# LPC1343_BaseBoard_V1_6.net
KiCad netlist of a schematic drawn in EAGLE
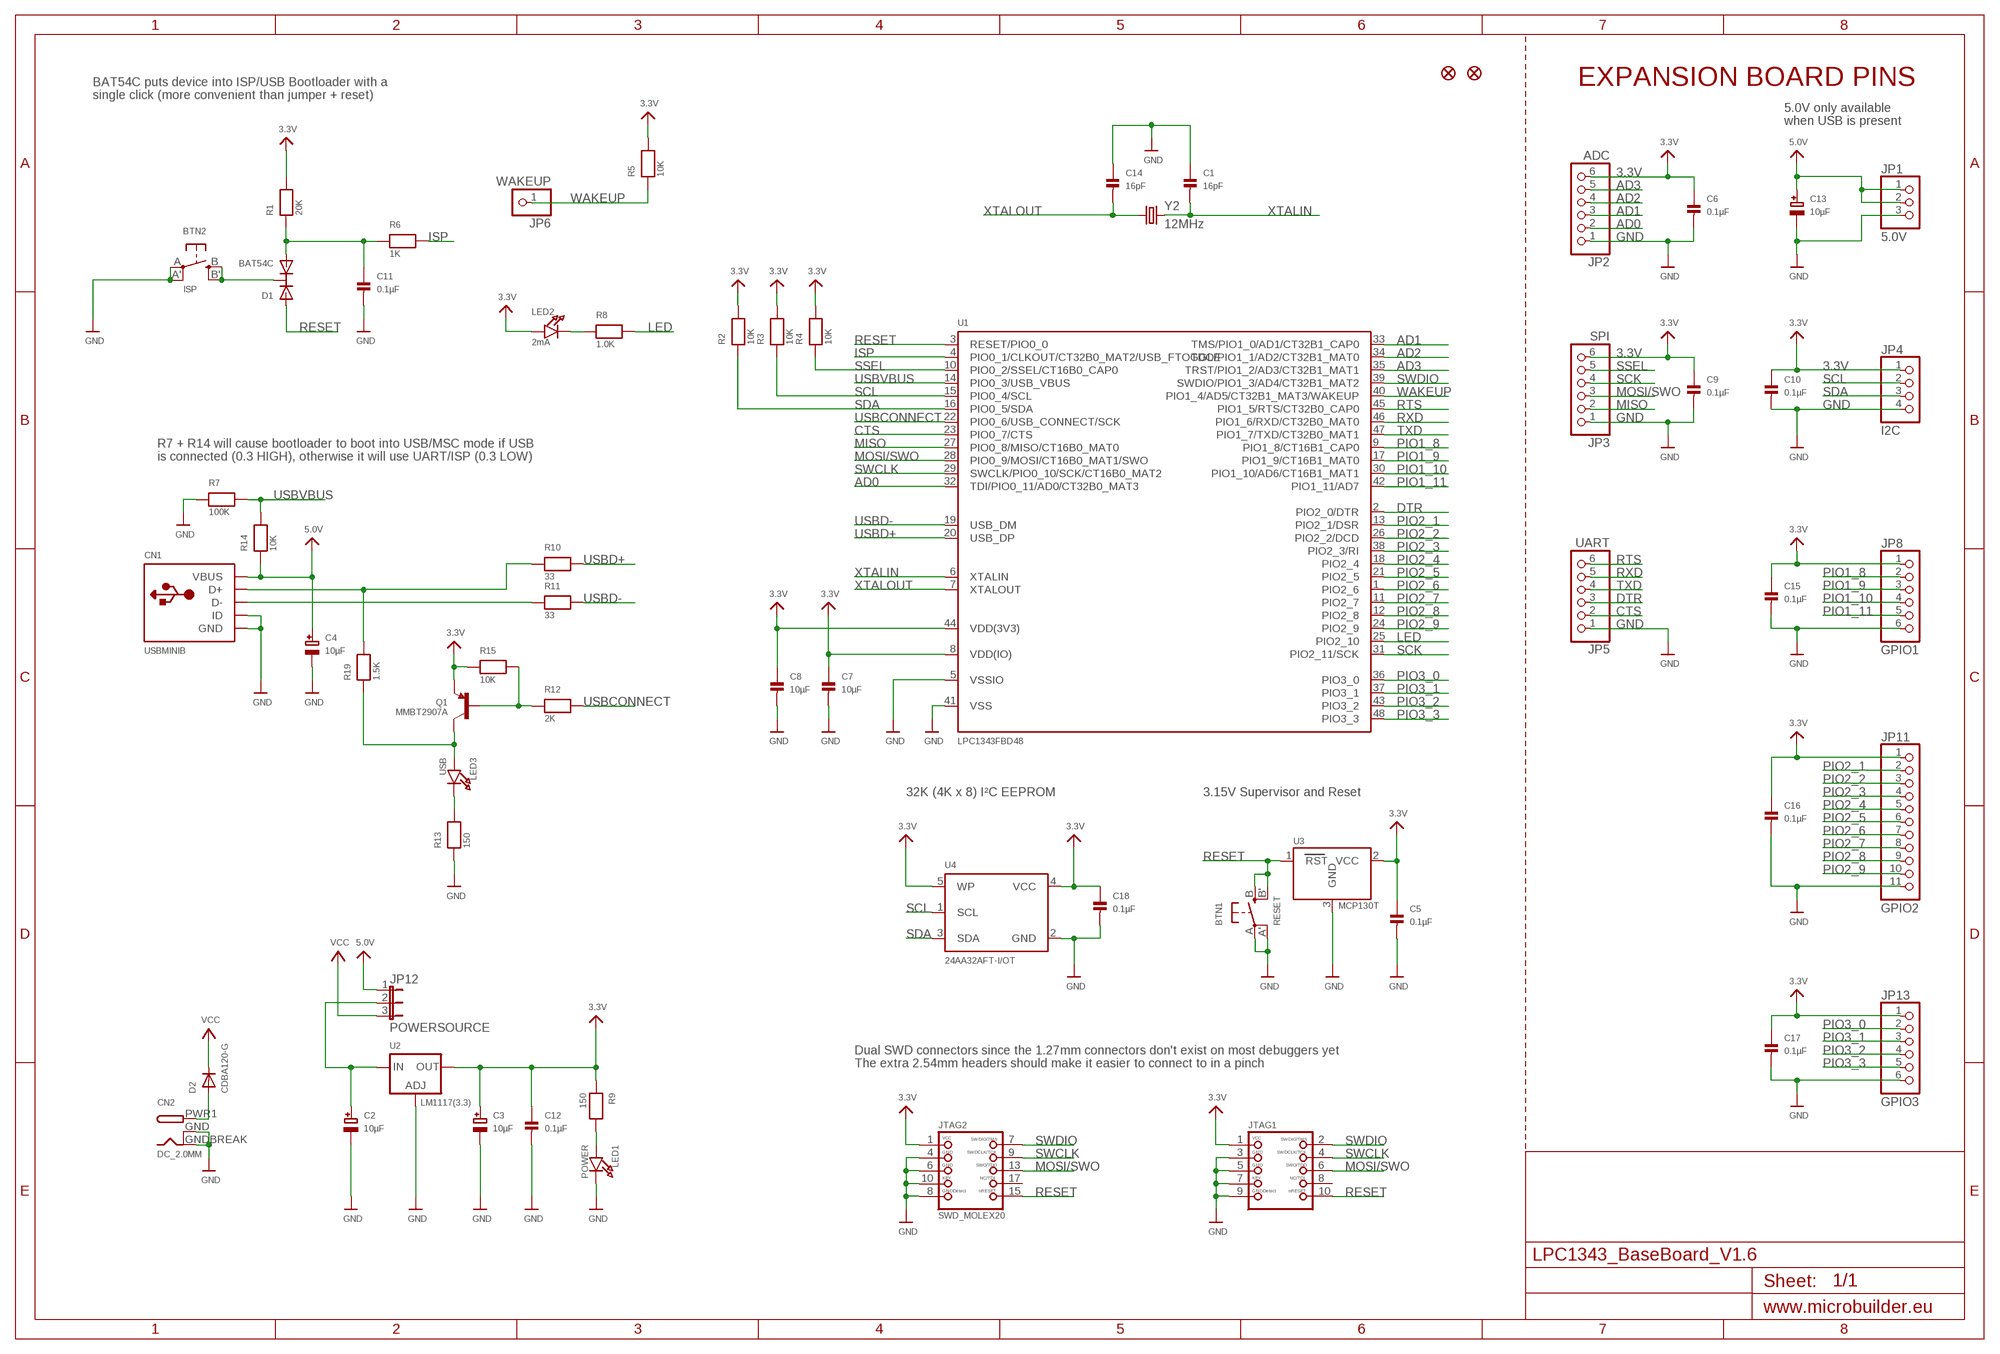
[diagram p0: schematic, sheet 1]

(export (version "E")
  (design (tool "Eeschema 10.0.6"))
  (components
    (comp (ref "BTN1")
      (value "RESET")
      (footprint "eagle-import:EVQ-Q2")
      (libsource (lib "eagle-import") (part "BUTTON_SMT"))
    )
    (comp (ref "BTN2")
      (value "ISP")
      (footprint "eagle-import:EVQ-Q2")
      (libsource (lib "eagle-import") (part "BUTTON_SMT"))
    )
    (comp (ref "C1")
      (value "16pF")
      (footprint "eagle-import:0603")
      (libsource (lib "eagle-import") (part "CAP_CERAMIC0603"))
    )
    (comp (ref "C2")
      (value "10µF")
      (footprint "eagle-import:EIA3216-18_A-R")
      (libsource (lib "eagle-import") (part "CAP_TANTALUMA/3216_REFLOW"))
    )
    (comp (ref "C3")
      (value "10µF")
      (footprint "eagle-import:EIA3216-18_A-R")
      (libsource (lib "eagle-import") (part "CAP_TANTALUMA/3216_REFLOW"))
    )
    (comp (ref "C4")
      (value "10µF")
      (footprint "eagle-import:EIA3216-18_A-R")
      (libsource (lib "eagle-import") (part "CAP_TANTALUMA/3216_REFLOW"))
    )
    (comp (ref "C5")
      (value "0.1µF")
      (footprint "eagle-import:0603")
      (libsource (lib "eagle-import") (part "CAP_CERAMIC0603"))
    )
    (comp (ref "C6")
      (value "0.1µF")
      (footprint "eagle-import:0603")
      (libsource (lib "eagle-import") (part "CAP_CERAMIC0603"))
    )
    (comp (ref "C7")
      (value "10µF")
      (footprint "eagle-import:0805")
      (libsource (lib "eagle-import") (part "CAP_CERAMIC0805"))
    )
    (comp (ref "C8")
      (value "10µF")
      (footprint "eagle-import:0805")
      (libsource (lib "eagle-import") (part "CAP_CERAMIC0805"))
    )
    (comp (ref "C9")
      (value "0.1µF")
      (footprint "eagle-import:0603")
      (libsource (lib "eagle-import") (part "CAP_CERAMIC0603"))
    )
    (comp (ref "C10")
      (value "0.1µF")
      (footprint "eagle-import:0603")
      (libsource (lib "eagle-import") (part "CAP_CERAMIC0603"))
    )
    (comp (ref "C11")
      (value "0.1µF")
      (footprint "eagle-import:0603")
      (libsource (lib "eagle-import") (part "CAP_CERAMIC0603"))
    )
    (comp (ref "C12")
      (value "0.1µF")
      (footprint "eagle-import:0603")
      (libsource (lib "eagle-import") (part "CAP_CERAMIC0603"))
    )
    (comp (ref "C13")
      (value "10µF")
      (footprint "eagle-import:EIA3216-18_A-R")
      (libsource (lib "eagle-import") (part "CAP_TANTALUMA/3216_REFLOW"))
    )
    (comp (ref "C14")
      (value "16pF")
      (footprint "eagle-import:0603")
      (libsource (lib "eagle-import") (part "CAP_CERAMIC0603"))
    )
    (comp (ref "C15")
      (value "0.1µF")
      (footprint "eagle-import:0603")
      (libsource (lib "eagle-import") (part "CAP_CERAMIC0603"))
    )
    (comp (ref "C16")
      (value "0.1µF")
      (footprint "eagle-import:0603")
      (libsource (lib "eagle-import") (part "CAP_CERAMIC0603"))
    )
    (comp (ref "C17")
      (value "0.1µF")
      (footprint "eagle-import:0603")
      (libsource (lib "eagle-import") (part "CAP_CERAMIC0603"))
    )
    (comp (ref "C18")
      (value "0.1µF")
      (footprint "eagle-import:0603")
      (libsource (lib "eagle-import") (part "CAP_CERAMIC0603"))
    )
    (comp (ref "CN1")
      (value "USBMINIB")
      (footprint "eagle-import:USB-MINIB")
      (libsource (lib "eagle-import") (part "USBMINIB"))
    )
    (comp (ref "CN2")
      (value "DC_2.0MM")
      (footprint "eagle-import:DCJACK_2MM_SMT")
      (libsource (lib "eagle-import") (part "DCBARRELSMT"))
    )
    (comp (ref "D1")
      (value "BAT54C")
      (footprint "eagle-import:SOT23-R")
      (libsource (lib "eagle-import") (part "BAT54C"))
    )
    (comp (ref "D2")
      (value "CDBA120-G")
      (footprint "eagle-import:SMADIODE")
      (libsource (lib "eagle-import") (part "DIODESMA"))
    )
    (comp (ref "JP1")
      (value "5.0V")
      (footprint "eagle-import:1X03_ROUND")
      (libsource (lib "eagle-import") (part "HEADER-1X3ROUND"))
    )
    (comp (ref "JP2")
      (value "ADC")
      (footprint "eagle-import:1X06_ROUND")
      (libsource (lib "eagle-import") (part "HEADER-1X6ROUND"))
    )
    (comp (ref "JP3")
      (value "SPI")
      (footprint "eagle-import:1X06_ROUND")
      (libsource (lib "eagle-import") (part "HEADER-1X6ROUND"))
    )
    (comp (ref "JP4")
      (value "I2C")
      (footprint "eagle-import:1X04_ROUND")
      (libsource (lib "eagle-import") (part "HEADER-1X4ROUND"))
    )
    (comp (ref "JP5")
      (value "UART")
      (footprint "eagle-import:1X06_ROUND")
      (libsource (lib "eagle-import") (part "HEADER-1X6ROUND"))
    )
    (comp (ref "JP6")
      (value "WAKEUP")
      (footprint "eagle-import:1X01_ROUND")
      (libsource (lib "eagle-import") (part "HEADER-1X1ROUND"))
    )
    (comp (ref "JP7")
      (value "FIDUCIAL1X2.5")
      (footprint "eagle-import:FIDUCIAL-1X2.5")
      (libsource (lib "eagle-import") (part "FIDUCIAL1X2.5"))
    )
    (comp (ref "JP8")
      (value "GPIO1")
      (footprint "eagle-import:1X06_ROUND")
      (libsource (lib "eagle-import") (part "HEADER-1X6ROUND"))
    )
    (comp (ref "JP9")
      (value "FIDUCIAL1X2.5")
      (footprint "eagle-import:FIDUCIAL-1X2.5")
      (libsource (lib "eagle-import") (part "FIDUCIAL1X2.5"))
    )
    (comp (ref "JP11")
      (value "GPIO2")
      (footprint "eagle-import:1X11_ROUND")
      (libsource (lib "eagle-import") (part "HEADER-1X11"))
    )
    (comp (ref "JP12")
      (value "POWERSOURCE")
      (footprint "eagle-import:JUMPER3")
      (libsource (lib "eagle-import") (part "JUMPER3"))
    )
    (comp (ref "JP13")
      (value "GPIO3")
      (footprint "eagle-import:1X06_ROUND")
      (libsource (lib "eagle-import") (part "HEADER-1X6ROUND"))
    )
    (comp (ref "JTAG1")
      (value "JTAG-CORTEXM3")
      (footprint "eagle-import:2X05_1.27MM_SMT")
      (libsource (lib "eagle-import") (part "JTAG-CORTEXM3"))
    )
    (comp (ref "JTAG2")
      (value "SWD_MOLEX20")
      (footprint "eagle-import:JTAG-ARM")
      (libsource (lib "eagle-import") (part "JTAG-CORTEXM3MOLEX20"))
    )
    (comp (ref "LED1")
      (value "POWER")
      (footprint "eagle-import:CHIPLED_0805")
      (libsource (lib "eagle-import") (part "LED0805"))
    )
    (comp (ref "LED2")
      (value "2mA")
      (footprint "eagle-import:CHIPLED_0805")
      (libsource (lib "eagle-import") (part "LED0805"))
    )
    (comp (ref "LED3")
      (value "USB")
      (footprint "eagle-import:CHIPLED_0805")
      (libsource (lib "eagle-import") (part "LED0805"))
    )
    (comp (ref "Q1")
      (value "MMBT2907A")
      (footprint "eagle-import:SOT23-R")
      (libsource (lib "eagle-import") (part "TRANSISTOR_PNPSOT23-REFLOW"))
    )
    (comp (ref "R1")
      (value "20K")
      (footprint "eagle-import:0603")
      (libsource (lib "eagle-import") (part "RESISTOR0603"))
    )
    (comp (ref "R2")
      (value "10K")
      (footprint "eagle-import:0603")
      (libsource (lib "eagle-import") (part "RESISTOR0603"))
    )
    (comp (ref "R3")
      (value "10K")
      (footprint "eagle-import:0603")
      (libsource (lib "eagle-import") (part "RESISTOR0603"))
    )
    (comp (ref "R4")
      (value "10K")
      (footprint "eagle-import:0603")
      (libsource (lib "eagle-import") (part "RESISTOR0603"))
    )
    (comp (ref "R5")
      (value "10K")
      (footprint "eagle-import:0603")
      (libsource (lib "eagle-import") (part "RESISTOR0603"))
    )
    (comp (ref "R6")
      (value "1K")
      (footprint "eagle-import:0603")
      (libsource (lib "eagle-import") (part "RESISTOR0603"))
    )
    (comp (ref "R7")
      (value "100K")
      (footprint "eagle-import:0603")
      (libsource (lib "eagle-import") (part "RESISTOR0603"))
    )
    (comp (ref "R8")
      (value "1.0K")
      (footprint "eagle-import:0603")
      (libsource (lib "eagle-import") (part "RESISTOR0603"))
    )
    (comp (ref "R9")
      (value "150")
      (footprint "eagle-import:0603")
      (libsource (lib "eagle-import") (part "RESISTOR0603"))
    )
    (comp (ref "R10")
      (value "33")
      (footprint "eagle-import:0603")
      (libsource (lib "eagle-import") (part "RESISTOR0603"))
    )
    (comp (ref "R11")
      (value "33")
      (footprint "eagle-import:0603")
      (libsource (lib "eagle-import") (part "RESISTOR0603"))
    )
    (comp (ref "R12")
      (value "2K")
      (footprint "eagle-import:0603")
      (libsource (lib "eagle-import") (part "RESISTOR0603"))
    )
    (comp (ref "R13")
      (value "150")
      (footprint "eagle-import:0603")
      (libsource (lib "eagle-import") (part "RESISTOR0603"))
    )
    (comp (ref "R14")
      (value "10K")
      (footprint "eagle-import:0603")
      (libsource (lib "eagle-import") (part "RESISTOR0603"))
    )
    (comp (ref "R15")
      (value "10K")
      (footprint "eagle-import:0603")
      (libsource (lib "eagle-import") (part "RESISTOR0603"))
    )
    (comp (ref "R19")
      (value "1.5K")
      (footprint "eagle-import:0603")
      (libsource (lib "eagle-import") (part "RESISTOR0603"))
    )
    (comp (ref "U1")
      (value "LPC1343FBD48")
      (footprint "eagle-import:LQFP48")
      (libsource (lib "eagle-import") (part "LPC1343_QFP"))
    )
    (comp (ref "U2")
      (value "LM1117(3.3)")
      (footprint "eagle-import:SOT223-R")
      (libsource (lib "eagle-import") (part "LM1117SOT223-REFLOW"))
    )
    (comp (ref "U3")
      (value "MCP130T")
      (footprint "eagle-import:SOT23-R")
      (libsource (lib "eagle-import") (part "MCP130TREFLOW"))
    )
    (comp (ref "U4")
      (value "24AA32AFT-I/OT")
      (footprint "eagle-import:SOT23-5")
      (libsource (lib "eagle-import") (part "MCP24AA32"))
    )
    (comp (ref "Y2")
      (value "12MHz")
      (footprint "eagle-import:HC49_S")
      (libsource (lib "eagle-import") (part "CRYSTALHC49S"))
    )
  )
  (nets
    (net (code "1") (name "/AD0") (class "Default")
      (node (ref "JP2") (pin "2") (pinfunction "2_2") (pintype "passive"))
      (node (ref "U1") (pin "32") (pinfunction "TDI/PIO0_11/AD0/CT32B0_MAT3_32") (pintype "bidirectional"))
    )
    (net (code "2") (name "/AD1") (class "Default")
      (node (ref "JP2") (pin "3") (pinfunction "3_3") (pintype "passive"))
      (node (ref "U1") (pin "33") (pinfunction "TMS/PIO1_0/AD1/CT32B1_CAP0_33") (pintype "bidirectional"))
    )
    (net (code "3") (name "/AD2") (class "Default")
      (node (ref "JP2") (pin "4") (pinfunction "4_4") (pintype "passive"))
      (node (ref "U1") (pin "34") (pinfunction "TDO/PIO1_1/AD2/CT32B1_MAT0_34") (pintype "bidirectional"))
    )
    (net (code "4") (name "/AD3") (class "Default")
      (node (ref "JP2") (pin "5") (pinfunction "5_5") (pintype "passive"))
      (node (ref "U1") (pin "35") (pinfunction "TRST/PIO1_2/AD3/CT32B1_MAT1_35") (pintype "bidirectional"))
    )
    (net (code "5") (name "/CTS") (class "Default")
      (node (ref "JP5") (pin "2") (pinfunction "2_2") (pintype "passive"))
      (node (ref "U1") (pin "23") (pinfunction "PIO0_7/CTS_23") (pintype "bidirectional"))
    )
    (net (code "6") (name "/DTR") (class "Default")
      (node (ref "JP5") (pin "3") (pinfunction "3_3") (pintype "passive"))
      (node (ref "U1") (pin "2") (pinfunction "PIO2_0/DTR_2") (pintype "bidirectional"))
    )
    (net (code "7") (name "/ISP") (class "Default")
      (node (ref "R6") (pin "2") (pinfunction "2_2") (pintype "passive"))
      (node (ref "U1") (pin "4") (pinfunction "PIO0_1/CLKOUT/CT32B0_MAT2/USB_FTOGGLE_4") (pintype "bidirectional"))
    )
    (net (code "8") (name "/LED") (class "Default")
      (node (ref "R8") (pin "2") (pinfunction "2_2") (pintype "passive"))
      (node (ref "U1") (pin "25") (pinfunction "PIO2_10_25") (pintype "bidirectional"))
    )
    (net (code "9") (name "/MISO") (class "Default")
      (node (ref "JP3") (pin "2") (pinfunction "2_2") (pintype "passive"))
      (node (ref "U1") (pin "27") (pinfunction "PIO0_8/MISO/CT16B0_MAT0_27") (pintype "bidirectional"))
    )
    (net (code "10") (name "/MOSI{slash}SWO") (class "Default")
      (node (ref "JP3") (pin "3") (pinfunction "3_3") (pintype "passive"))
      (node (ref "JTAG1") (pin "6") (pinfunction "6_6") (pintype "passive"))
      (node (ref "JTAG2") (pin "13") (pinfunction "6_13") (pintype "passive"))
      (node (ref "U1") (pin "28") (pinfunction "PIO0_9/MOSI/CT16B0_MAT1/SWO_28") (pintype "bidirectional"))
    )
    (net (code "11") (name "/PIO1_8") (class "Default")
      (node (ref "JP8") (pin "2") (pinfunction "2_2") (pintype "passive"))
      (node (ref "U1") (pin "9") (pinfunction "PIO1_8/CT16B1_CAP0_9") (pintype "bidirectional"))
    )
    (net (code "12") (name "/PIO1_9") (class "Default")
      (node (ref "JP8") (pin "3") (pinfunction "3_3") (pintype "passive"))
      (node (ref "U1") (pin "17") (pinfunction "PIO1_9/CT16B1_MAT0_17") (pintype "bidirectional"))
    )
    (net (code "13") (name "/PIO1_10") (class "Default")
      (node (ref "JP8") (pin "4") (pinfunction "4_4") (pintype "passive"))
      (node (ref "U1") (pin "30") (pinfunction "PIO1_10/AD6/CT16B1_MAT1_30") (pintype "bidirectional"))
    )
    (net (code "14") (name "/PIO1_11") (class "Default")
      (node (ref "JP8") (pin "5") (pinfunction "5_5") (pintype "passive"))
      (node (ref "U1") (pin "42") (pinfunction "PIO1_11/AD7_42") (pintype "bidirectional"))
    )
    (net (code "15") (name "/PIO2_1") (class "Default")
      (node (ref "JP11") (pin "2") (pinfunction "2_2") (pintype "passive"))
      (node (ref "U1") (pin "13") (pinfunction "PIO2_1/DSR_13") (pintype "bidirectional"))
    )
    (net (code "16") (name "/PIO2_2") (class "Default")
      (node (ref "JP11") (pin "3") (pinfunction "3_3") (pintype "passive"))
      (node (ref "U1") (pin "26") (pinfunction "PIO2_2/DCD_26") (pintype "bidirectional"))
    )
    (net (code "17") (name "/PIO2_3") (class "Default")
      (node (ref "JP11") (pin "4") (pinfunction "4_4") (pintype "passive"))
      (node (ref "U1") (pin "38") (pinfunction "PIO2_3/RI_38") (pintype "bidirectional"))
    )
    (net (code "18") (name "/PIO2_4") (class "Default")
      (node (ref "JP11") (pin "5") (pinfunction "5_5") (pintype "passive"))
      (node (ref "U1") (pin "18") (pinfunction "PIO2_4_18") (pintype "bidirectional"))
    )
    (net (code "19") (name "/PIO2_5") (class "Default")
      (node (ref "JP11") (pin "6") (pinfunction "6_6") (pintype "passive"))
      (node (ref "U1") (pin "21") (pinfunction "PIO2_5_21") (pintype "bidirectional"))
    )
    (net (code "20") (name "/PIO2_6") (class "Default")
      (node (ref "JP11") (pin "7") (pinfunction "7_7") (pintype "passive"))
      (node (ref "U1") (pin "1") (pinfunction "PIO2_6_1") (pintype "bidirectional"))
    )
    (net (code "21") (name "/PIO2_7") (class "Default")
      (node (ref "JP11") (pin "8") (pinfunction "8_8") (pintype "passive"))
      (node (ref "U1") (pin "11") (pinfunction "PIO2_7_11") (pintype "bidirectional"))
    )
    (net (code "22") (name "/PIO2_8") (class "Default")
      (node (ref "JP11") (pin "9") (pinfunction "9_9") (pintype "passive"))
      (node (ref "U1") (pin "12") (pinfunction "PIO2_8_12") (pintype "bidirectional"))
    )
    (net (code "23") (name "/PIO2_9") (class "Default")
      (node (ref "JP11") (pin "10") (pinfunction "10_10") (pintype "passive"))
      (node (ref "U1") (pin "24") (pinfunction "PIO2_9_24") (pintype "bidirectional"))
    )
    (net (code "24") (name "/PIO3_0") (class "Default")
      (node (ref "JP13") (pin "2") (pinfunction "2_2") (pintype "passive"))
      (node (ref "U1") (pin "36") (pinfunction "PIO3_0_36") (pintype "bidirectional"))
    )
    (net (code "25") (name "/PIO3_1") (class "Default")
      (node (ref "JP13") (pin "3") (pinfunction "3_3") (pintype "passive"))
      (node (ref "U1") (pin "37") (pinfunction "PIO3_1_37") (pintype "bidirectional"))
    )
    (net (code "26") (name "/PIO3_2") (class "Default")
      (node (ref "JP13") (pin "4") (pinfunction "4_4") (pintype "passive"))
      (node (ref "U1") (pin "43") (pinfunction "PIO3_2_43") (pintype "bidirectional"))
    )
    (net (code "27") (name "/PIO3_3") (class "Default")
      (node (ref "JP13") (pin "5") (pinfunction "5_5") (pintype "passive"))
      (node (ref "U1") (pin "48") (pinfunction "PIO3_3_48") (pintype "bidirectional"))
    )
    (net (code "28") (name "/RESET") (class "Default")
      (node (ref "BTN1") (pin "B") (pinfunction "S_B") (pintype "passive"))
      (node (ref "BTN1") (pin "B'") (pinfunction "S1_B'") (pintype "passive"))
      (node (ref "D1") (pin "1") (pinfunction "A1_1") (pintype "passive"))
      (node (ref "JTAG1") (pin "10") (pinfunction "10_10") (pintype "passive"))
      (node (ref "JTAG2") (pin "15") (pinfunction "10_15") (pintype "passive"))
      (node (ref "U1") (pin "3") (pinfunction "RESET/PIO0_0_3") (pintype "bidirectional"))
      (node (ref "U3") (pin "1") (pinfunction "RST_1") (pintype "bidirectional"))
    )
    (net (code "29") (name "/RTS") (class "Default")
      (node (ref "JP5") (pin "6") (pinfunction "6_6") (pintype "passive"))
      (node (ref "U1") (pin "45") (pinfunction "PIO1_5/RTS/CT32B0_CAP0_45") (pintype "bidirectional"))
    )
    (net (code "30") (name "/RXD") (class "Default")
      (node (ref "JP5") (pin "5") (pinfunction "5_5") (pintype "passive"))
      (node (ref "U1") (pin "46") (pinfunction "PIO1_6/RXD/CT32B0_MAT0_46") (pintype "bidirectional"))
    )
    (net (code "31") (name "/SCK") (class "Default")
      (node (ref "JP3") (pin "4") (pinfunction "4_4") (pintype "passive"))
      (node (ref "U1") (pin "31") (pinfunction "PIO2_11/SCK_31") (pintype "bidirectional"))
    )
    (net (code "32") (name "/SCL") (class "Default")
      (node (ref "JP4") (pin "2") (pinfunction "2_2") (pintype "passive"))
      (node (ref "R3") (pin "1") (pinfunction "1_1") (pintype "passive"))
      (node (ref "U1") (pin "15") (pinfunction "PIO0_4/SCL_15") (pintype "bidirectional"))
      (node (ref "U4") (pin "1") (pinfunction "SCL_1") (pintype "bidirectional"))
    )
    (net (code "33") (name "/SDA") (class "Default")
      (node (ref "JP4") (pin "3") (pinfunction "3_3") (pintype "passive"))
      (node (ref "R2") (pin "1") (pinfunction "1_1") (pintype "passive"))
      (node (ref "U1") (pin "16") (pinfunction "PIO0_5/SDA_16") (pintype "bidirectional"))
      (node (ref "U4") (pin "3") (pinfunction "SDA_3") (pintype "bidirectional"))
    )
    (net (code "34") (name "/SSEL") (class "Default")
      (node (ref "JP3") (pin "5") (pinfunction "5_5") (pintype "passive"))
      (node (ref "R4") (pin "1") (pinfunction "1_1") (pintype "passive"))
      (node (ref "U1") (pin "10") (pinfunction "PIO0_2/SSEL/CT16B0_CAP0_10") (pintype "bidirectional"))
    )
    (net (code "35") (name "/SWCLK") (class "Default")
      (node (ref "JTAG1") (pin "4") (pinfunction "4_4") (pintype "passive"))
      (node (ref "JTAG2") (pin "9") (pinfunction "4_9") (pintype "passive"))
      (node (ref "U1") (pin "29") (pinfunction "SWCLK/PIO0_10/SCK/CT16B0_MAT2_29") (pintype "bidirectional"))
    )
    (net (code "36") (name "/SWDIO") (class "Default")
      (node (ref "JTAG1") (pin "2") (pinfunction "2_2") (pintype "passive"))
      (node (ref "JTAG2") (pin "7") (pinfunction "2_7") (pintype "passive"))
      (node (ref "U1") (pin "39") (pinfunction "SWDIO/PIO1_3/AD4/CT32B1_MAT2_39") (pintype "bidirectional"))
    )
    (net (code "37") (name "/TXD") (class "Default")
      (node (ref "JP5") (pin "4") (pinfunction "4_4") (pintype "passive"))
      (node (ref "U1") (pin "47") (pinfunction "PIO1_7/TXD/CT32B0_MAT1_47") (pintype "bidirectional"))
    )
    (net (code "38") (name "/USBCONNECT") (class "Default")
      (node (ref "R12") (pin "2") (pinfunction "2_2") (pintype "passive"))
      (node (ref "U1") (pin "22") (pinfunction "PIO0_6/USB_CONNECT/SCK_22") (pintype "bidirectional"))
    )
    (net (code "39") (name "/USBD+") (class "Default")
      (node (ref "R10") (pin "2") (pinfunction "2_2") (pintype "passive"))
      (node (ref "U1") (pin "20") (pinfunction "USB_DP_20") (pintype "bidirectional"))
    )
    (net (code "40") (name "/USBD-") (class "Default")
      (node (ref "R11") (pin "2") (pinfunction "2_2") (pintype "passive"))
      (node (ref "U1") (pin "19") (pinfunction "USB_DM_19") (pintype "bidirectional"))
    )
    (net (code "41") (name "/USBVBUS") (class "Default")
      (node (ref "R14") (pin "2") (pinfunction "2_2") (pintype "passive"))
      (node (ref "R7") (pin "2") (pinfunction "2_2") (pintype "passive"))
      (node (ref "U1") (pin "14") (pinfunction "PIO0_3/USB_VBUS_14") (pintype "bidirectional"))
    )
    (net (code "42") (name "/WAKEUP") (class "Default")
      (node (ref "JP6") (pin "1") (pinfunction "1_1") (pintype "passive"))
      (node (ref "R5") (pin "1") (pinfunction "1_1") (pintype "passive"))
      (node (ref "U1") (pin "40") (pinfunction "PIO1_4/AD5/CT32B1_MAT3/WAKEUP_40") (pintype "bidirectional"))
    )
    (net (code "43") (name "/XTALIN") (class "Default")
      (node (ref "C1") (pin "2") (pinfunction "P$2_2") (pintype "passive"))
      (node (ref "U1") (pin "6") (pinfunction "XTALIN_6") (pintype "input"))
      (node (ref "Y2") (pin "2") (pinfunction "2_2") (pintype "passive"))
    )
    (net (code "44") (name "/XTALOUT") (class "Default")
      (node (ref "C14") (pin "2") (pinfunction "P$2_2") (pintype "passive"))
      (node (ref "U1") (pin "7") (pinfunction "XTALOUT_7") (pintype "output"))
      (node (ref "Y2") (pin "1") (pinfunction "1_1") (pintype "passive"))
    )
    (net (code "45") (name "3.3V") (class "Default")
      (node (ref "C10") (pin "1") (pinfunction "P$1_1") (pintype "passive"))
      (node (ref "C12") (pin "1") (pinfunction "P$1_1") (pintype "passive"))
      (node (ref "C15") (pin "1") (pinfunction "P$1_1") (pintype "passive"))
      (node (ref "C16") (pin "1") (pinfunction "P$1_1") (pintype "passive"))
      (node (ref "C17") (pin "1") (pinfunction "P$1_1") (pintype "passive"))
      (node (ref "C18") (pin "1") (pinfunction "P$1_1") (pintype "passive"))
      (node (ref "C3") (pin "+") (pinfunction "+_+") (pintype "passive"))
      (node (ref "C5") (pin "1") (pinfunction "P$1_1") (pintype "passive"))
      (node (ref "C6") (pin "1") (pinfunction "P$1_1") (pintype "passive"))
      (node (ref "C7") (pin "1") (pinfunction "P$1_1") (pintype "passive"))
      (node (ref "C8") (pin "1") (pinfunction "P$1_1") (pintype "passive"))
      (node (ref "C9") (pin "1") (pinfunction "P$1_1") (pintype "passive"))
      (node (ref "JP11") (pin "1") (pinfunction "1_1") (pintype "passive"))
      (node (ref "JP13") (pin "1") (pinfunction "1_1") (pintype "passive"))
      (node (ref "JP2") (pin "6") (pinfunction "6_6") (pintype "passive"))
      (node (ref "JP3") (pin "6") (pinfunction "6_6") (pintype "passive"))
      (node (ref "JP4") (pin "1") (pinfunction "1_1") (pintype "passive"))
      (node (ref "JP8") (pin "1") (pinfunction "1_1") (pintype "passive"))
      (node (ref "JTAG1") (pin "1") (pinfunction "1_1") (pintype "passive"))
      (node (ref "JTAG2") (pin "1") (pinfunction "1_1") (pintype "passive"))
      (node (ref "LED2") (pin "A") (pinfunction "A_A") (pintype "passive"))
      (node (ref "Q1") (pin "2") (pinfunction "E_2") (pintype "passive"))
      (node (ref "R1") (pin "2") (pinfunction "2_2") (pintype "passive"))
      (node (ref "R15") (pin "1") (pinfunction "1_1") (pintype "passive"))
      (node (ref "R2") (pin "2") (pinfunction "2_2") (pintype "passive"))
      (node (ref "R3") (pin "2") (pinfunction "2_2") (pintype "passive"))
      (node (ref "R4") (pin "2") (pinfunction "2_2") (pintype "passive"))
      (node (ref "R5") (pin "2") (pinfunction "2_2") (pintype "passive"))
      (node (ref "R9") (pin "1") (pinfunction "1_1") (pintype "passive"))
      (node (ref "U1") (pin "44") (pinfunction "VDD(3V3)_44") (pintype "power_in"))
      (node (ref "U1") (pin "8") (pinfunction "VDD(IO)_8") (pintype "power_in"))
      (node (ref "U2") (pin "2") (pinfunction "OUT_2") (pintype "passive"))
      (node (ref "U3") (pin "2") (pinfunction "VCC_2") (pintype "power_in"))
      (node (ref "U4") (pin "4") (pinfunction "VCC_4") (pintype "bidirectional"))
      (node (ref "U4") (pin "5") (pinfunction "WP_5") (pintype "bidirectional"))
    )
    (net (code "46") (name "5.0V") (class "Default")
      (node (ref "C13") (pin "+") (pinfunction "+_+") (pintype "passive"))
      (node (ref "C4") (pin "+") (pinfunction "+_+") (pintype "passive"))
      (node (ref "CN1") (pin "VBUS") (pinfunction "VBUS_VBUS") (pintype "power_in"))
      (node (ref "JP1") (pin "1") (pinfunction "1_1") (pintype "passive"))
      (node (ref "JP1") (pin "2") (pinfunction "2_2") (pintype "passive"))
      (node (ref "JP12") (pin "1") (pinfunction "1_1") (pintype "passive"))
      (node (ref "R14") (pin "1") (pinfunction "1_1") (pintype "passive"))
    )
    (net (code "47") (name "GND") (class "Default")
      (node (ref "BTN1") (pin "A") (pinfunction "P_A") (pintype "passive"))
      (node (ref "BTN1") (pin "A'") (pinfunction "P1_A'") (pintype "passive"))
      (node (ref "BTN2") (pin "A") (pinfunction "P_A") (pintype "passive"))
      (node (ref "BTN2") (pin "A'") (pinfunction "P1_A'") (pintype "passive"))
      (node (ref "C1") (pin "1") (pinfunction "P$1_1") (pintype "passive"))
      (node (ref "C10") (pin "2") (pinfunction "P$2_2") (pintype "passive"))
      (node (ref "C11") (pin "2") (pinfunction "P$2_2") (pintype "passive"))
      (node (ref "C12") (pin "2") (pinfunction "P$2_2") (pintype "passive"))
      (node (ref "C13") (pin "-") (pinfunction "-_-") (pintype "passive"))
      (node (ref "C14") (pin "1") (pinfunction "P$1_1") (pintype "passive"))
      (node (ref "C15") (pin "2") (pinfunction "P$2_2") (pintype "passive"))
      (node (ref "C16") (pin "2") (pinfunction "P$2_2") (pintype "passive"))
      (node (ref "C17") (pin "2") (pinfunction "P$2_2") (pintype "passive"))
      (node (ref "C18") (pin "2") (pinfunction "P$2_2") (pintype "passive"))
      (node (ref "C2") (pin "-") (pinfunction "-_-") (pintype "passive"))
      (node (ref "C3") (pin "-") (pinfunction "-_-") (pintype "passive"))
      (node (ref "C4") (pin "-") (pinfunction "-_-") (pintype "passive"))
      (node (ref "C5") (pin "2") (pinfunction "P$2_2") (pintype "passive"))
      (node (ref "C6") (pin "2") (pinfunction "P$2_2") (pintype "passive"))
      (node (ref "C7") (pin "2") (pinfunction "P$2_2") (pintype "passive"))
      (node (ref "C8") (pin "2") (pinfunction "P$2_2") (pintype "passive"))
      (node (ref "C9") (pin "2") (pinfunction "P$2_2") (pintype "passive"))
      (node (ref "CN1") (pin "GND") (pinfunction "GND_GND") (pintype "power_in"))
      (node (ref "CN1") (pin "ID") (pinfunction "ID_ID") (pintype "bidirectional"))
      (node (ref "CN2") (pin "GND") (pinfunction "GNDBREAK_GND") (pintype "power_in"))
      (node (ref "CN2") (pin "GNDBREAK") (pinfunction "GND_GNDBREAK") (pintype "power_in"))
      (node (ref "JP1") (pin "3") (pinfunction "3_3") (pintype "passive"))
      (node (ref "JP11") (pin "11") (pinfunction "11_11") (pintype "passive"))
      (node (ref "JP13") (pin "6") (pinfunction "6_6") (pintype "passive"))
      (node (ref "JP2") (pin "1") (pinfunction "1_1") (pintype "passive"))
      (node (ref "JP3") (pin "1") (pinfunction "1_1") (pintype "passive"))
      (node (ref "JP4") (pin "4") (pinfunction "4_4") (pintype "passive"))
      (node (ref "JP5") (pin "1") (pinfunction "1_1") (pintype "passive"))
      (node (ref "JP8") (pin "6") (pinfunction "6_6") (pintype "passive"))
      (node (ref "JTAG1") (pin "3") (pinfunction "3_3") (pintype "passive"))
      (node (ref "JTAG1") (pin "5") (pinfunction "5_5") (pintype "passive"))
      (node (ref "JTAG1") (pin "7") (pinfunction "7_7") (pintype "passive"))
      (node (ref "JTAG1") (pin "9") (pinfunction "9_9") (pintype "passive"))
      (node (ref "JTAG2") (pin "10") (pinfunction "7_10") (pintype "passive"))
      (node (ref "JTAG2") (pin "4") (pinfunction "3_4") (pintype "passive"))
      (node (ref "JTAG2") (pin "6") (pinfunction "5_6") (pintype "passive"))
      (node (ref "JTAG2") (pin "8") (pinfunction "9_8") (pintype "passive"))
      (node (ref "LED1") (pin "C") (pinfunction "C_C") (pintype "passive"))
      (node (ref "R13") (pin "1") (pinfunction "1_1") (pintype "passive"))
      (node (ref "R7") (pin "1") (pinfunction "1_1") (pintype "passive"))
      (node (ref "U1") (pin "41") (pinfunction "VSS_41") (pintype "power_in"))
      (node (ref "U1") (pin "5") (pinfunction "VSSIO_5") (pintype "power_in"))
      (node (ref "U2") (pin "1") (pinfunction "ADJ_1") (pintype "input"))
      (node (ref "U3") (pin "3") (pinfunction "GND_3") (pintype "power_in"))
      (node (ref "U4") (pin "2") (pinfunction "GND_2") (pintype "bidirectional"))
    )
    (net (code "48") (name "Net-(BTN2-S)") (class "Default")
      (node (ref "BTN2") (pin "B") (pinfunction "S_B") (pintype "passive"))
      (node (ref "BTN2") (pin "B'") (pinfunction "S1_B'") (pintype "passive"))
      (node (ref "D1") (pin "3") (pinfunction "C_3") (pintype "passive"))
    )
    (net (code "49") (name "Net-(C11-P$1)") (class "Default")
      (node (ref "C11") (pin "1") (pinfunction "P$1_1") (pintype "passive"))
      (node (ref "D1") (pin "2") (pinfunction "A2_2") (pintype "passive"))
      (node (ref "R1") (pin "1") (pinfunction "1_1") (pintype "passive"))
      (node (ref "R6") (pin "1") (pinfunction "1_1") (pintype "passive"))
    )
    (net (code "50") (name "Net-(CN1-PadD+)") (class "Default")
      (node (ref "CN1") (pin "D+") (pinfunction "D+_D+") (pintype "bidirectional"))
      (node (ref "R10") (pin "1") (pinfunction "1_1") (pintype "passive"))
      (node (ref "R19") (pin "2") (pinfunction "2_2") (pintype "passive"))
    )
    (net (code "51") (name "Net-(CN1-PadD-)") (class "Default")
      (node (ref "CN1") (pin "D-") (pinfunction "D-_D-") (pintype "bidirectional"))
      (node (ref "R11") (pin "1") (pinfunction "1_1") (pintype "passive"))
    )
    (net (code "52") (name "Net-(CN2-PWR)") (class "Default")
      (node (ref "CN2") (pin "PWR1") (pinfunction "PWR_PWR1") (pintype "power_in"))
      (node (ref "D2") (pin "A") (pinfunction "A_A") (pintype "passive"))
    )
    (net (code "53") (name "Net-(LED1-PadA)") (class "Default")
      (node (ref "LED1") (pin "A") (pinfunction "A_A") (pintype "passive"))
      (node (ref "R9") (pin "2") (pinfunction "2_2") (pintype "passive"))
    )
    (net (code "54") (name "Net-(LED2-PadC)") (class "Default")
      (node (ref "LED2") (pin "C") (pinfunction "C_C") (pintype "passive"))
      (node (ref "R8") (pin "1") (pinfunction "1_1") (pintype "passive"))
    )
    (net (code "55") (name "Net-(LED3-PadC)") (class "Default")
      (node (ref "LED3") (pin "C") (pinfunction "C_C") (pintype "passive"))
      (node (ref "R13") (pin "2") (pinfunction "2_2") (pintype "passive"))
    )
    (net (code "56") (name "Net-(Q1-B)") (class "Default")
      (node (ref "Q1") (pin "1") (pinfunction "B_1") (pintype "passive"))
      (node (ref "R12") (pin "1") (pinfunction "1_1") (pintype "passive"))
      (node (ref "R15") (pin "2") (pinfunction "2_2") (pintype "passive"))
    )
    (net (code "57") (name "Net-(Q1-C)") (class "Default")
      (node (ref "LED3") (pin "A") (pinfunction "A_A") (pintype "passive"))
      (node (ref "Q1") (pin "3") (pinfunction "C_3") (pintype "passive"))
      (node (ref "R19") (pin "1") (pinfunction "1_1") (pintype "passive"))
    )
    (net (code "58") (name "Net-(U2-IN)") (class "Default")
      (node (ref "C2") (pin "+") (pinfunction "+_+") (pintype "passive"))
      (node (ref "JP12") (pin "2") (pinfunction "2_2") (pintype "passive"))
      (node (ref "U2") (pin "3") (pinfunction "IN_3") (pintype "input"))
    )
    (net (code "59") (name "VCC") (class "Default")
      (node (ref "D2") (pin "C") (pinfunction "C_C") (pintype "passive"))
      (node (ref "JP12") (pin "3") (pinfunction "3_3") (pintype "passive"))
    )
    (net (code "60") (name "unconnected-(JTAG1-Pad8)") (class "Default")
      (node (ref "JTAG1") (pin "8") (pinfunction "8_8") (pintype "passive"))
    )
    (net (code "61") (name "unconnected-(JTAG2-8-Pad17)") (class "Default")
      (node (ref "JTAG2") (pin "17") (pinfunction "8_17") (pintype "passive"))
    )
  )
)
